# SomUSB2.net
KiCad netlist of a schematic drawn in EAGLE
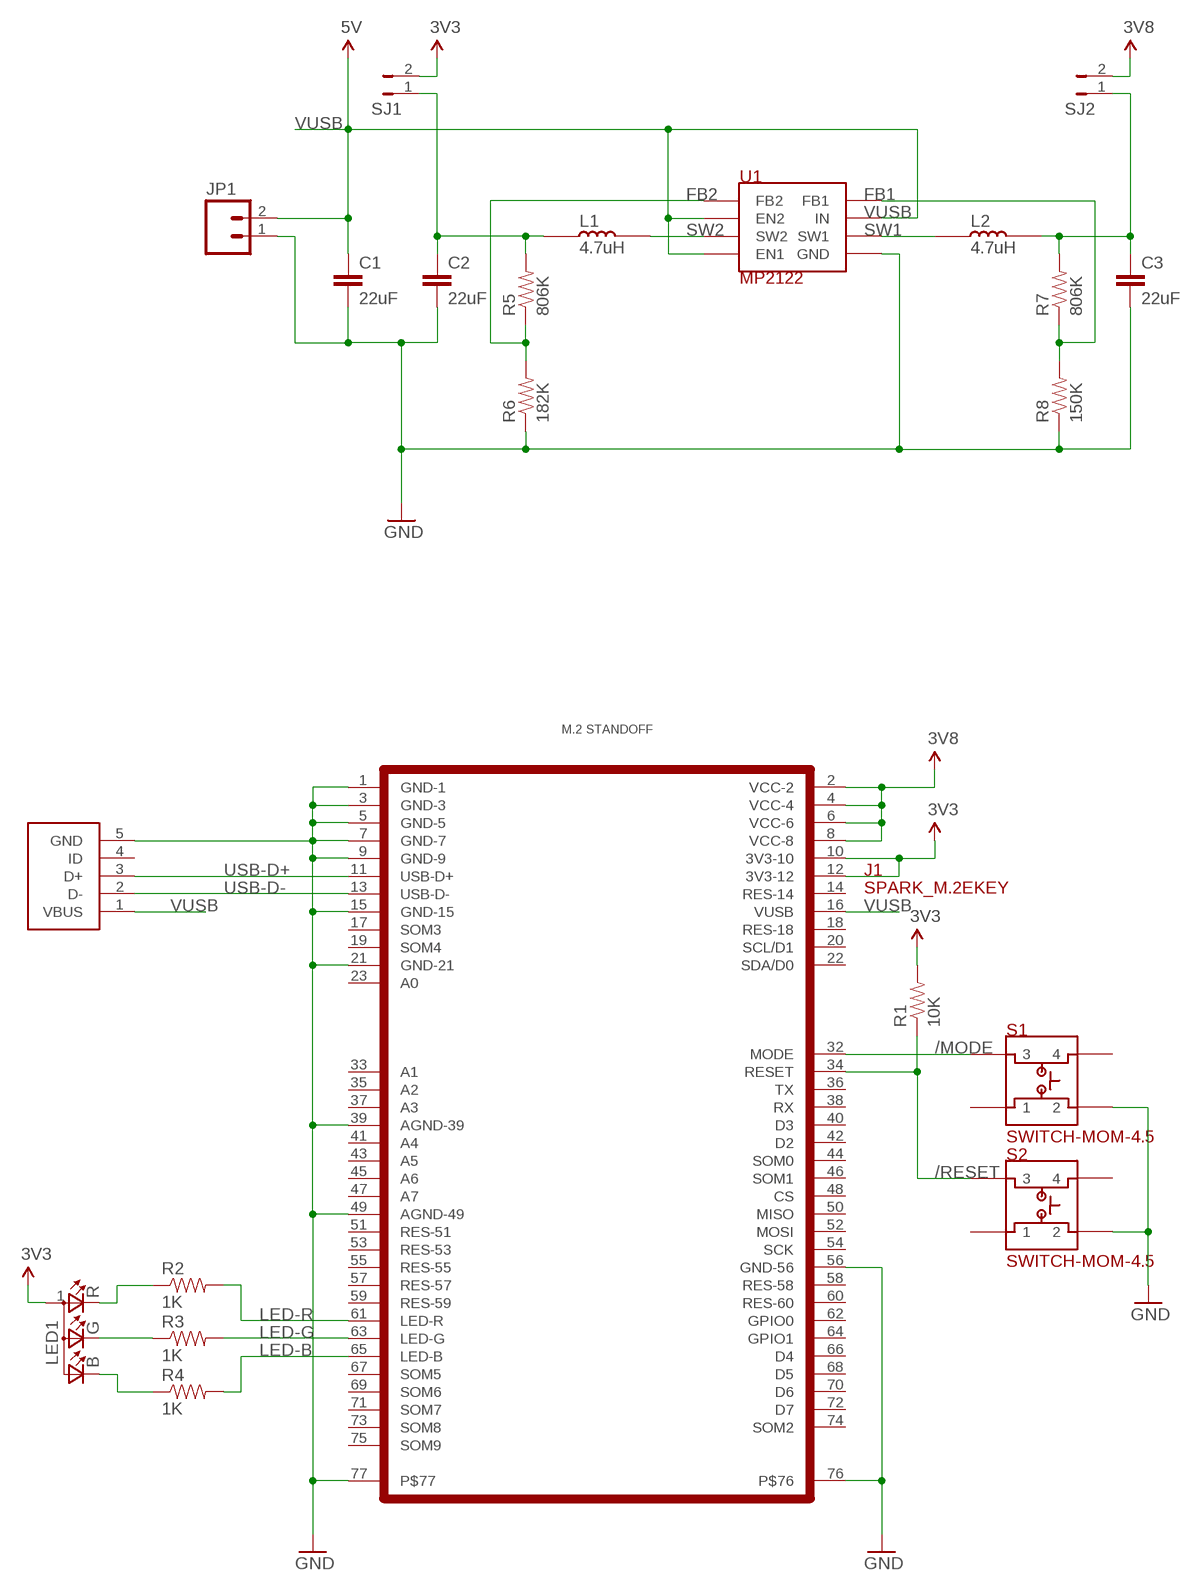
[diagram p0: schematic, sheet 1]

(export (version "E")
  (design (tool "Eeschema 10.0.6"))
  (components
    (comp (ref "C1")
      (value "22uF")
      (footprint "eagle-import:0805")
      (libsource (lib "eagle-import") (part "CAP-22UF-0805"))
    )
    (comp (ref "C2")
      (value "22uF")
      (footprint "eagle-import:0805")
      (libsource (lib "eagle-import") (part "CAP-22UF-0805"))
    )
    (comp (ref "C3")
      (value "22uF")
      (footprint "eagle-import:0805")
      (libsource (lib "eagle-import") (part "CAP-22UF-0805"))
    )
    (comp (ref "J1")
      (value "SPARK_M.2EKEY")
      (footprint "eagle-import:SPARK_M.2EKEY-LESS-CREAM")
      (libsource (lib "eagle-import") (part "SPARK_M.2EKEY"))
    )
    (comp (ref "JP1")
      (value "M02PTH")
      (footprint "eagle-import:1X02")
      (libsource (lib "eagle-import") (part "M02PTH"))
    )
    (comp (ref "L1")
      (value "4.7uH")
      (footprint "eagle-import:1008-BOURNS")
      (libsource (lib "eagle-import") (part "INDUCTOR-4.7UH"))
    )
    (comp (ref "L2")
      (value "4.7uH")
      (footprint "eagle-import:1008-BOURNS")
      (libsource (lib "eagle-import") (part "INDUCTOR-4.7UH"))
    )
    (comp (ref "LED1")
      (value "LED-RGB-CREE-SMD")
      (footprint "eagle-import:LED-RGB-CREE-SMD")
      (libsource (lib "eagle-import") (part "LED-RGB-CREE-SMD"))
    )
    (comp (ref "R1")
      (value "10K")
      (footprint "eagle-import:0603-RES")
      (libsource (lib "eagle-import") (part "RES-10K-06030603"))
    )
    (comp (ref "R2")
      (value "1K")
      (footprint "eagle-import:0603-RES")
      (libsource (lib "eagle-import") (part "RES-1K-0603"))
    )
    (comp (ref "R3")
      (value "1K")
      (footprint "eagle-import:0603-RES")
      (libsource (lib "eagle-import") (part "RES-1K-0603"))
    )
    (comp (ref "R4")
      (value "1K")
      (footprint "eagle-import:0603-RES")
      (libsource (lib "eagle-import") (part "RES-1K-0603"))
    )
    (comp (ref "R5")
      (value "806K")
      (footprint "eagle-import:0603-RES")
      (libsource (lib "eagle-import") (part "RES-806K-0603"))
    )
    (comp (ref "R6")
      (value "182K")
      (footprint "eagle-import:0603-RES")
      (libsource (lib "eagle-import") (part "RES-182K-0603"))
    )
    (comp (ref "R7")
      (value "806K")
      (footprint "eagle-import:0603-RES")
      (libsource (lib "eagle-import") (part "RES-806K-0603"))
    )
    (comp (ref "R8")
      (value "150K")
      (footprint "eagle-import:0603-RES")
      (libsource (lib "eagle-import") (part "RES-150K-0603"))
    )
    (comp (ref "S1")
      (value "SWITCH-MOM-4.5")
      (footprint "eagle-import:SWITCH-MOM-4.5")
      (libsource (lib "eagle-import") (part "SWITCH-MOM-4.5"))
    )
    (comp (ref "S2")
      (value "SWITCH-MOM-4.5")
      (footprint "eagle-import:SWITCH-MOM-4.5")
      (libsource (lib "eagle-import") (part "SWITCH-MOM-4.5"))
    )
    (comp (ref "SJ1")
      (value "JUMPER-PTH-2-NO")
      (footprint "eagle-import:PTH-JUMPER-2-NO_NO_SILK")
      (libsource (lib "eagle-import") (part "JUMPER-PTH-2-NO"))
    )
    (comp (ref "SJ2")
      (value "JUMPER-PTH-2-NO")
      (footprint "eagle-import:PTH-JUMPER-2-NO_NO_SILK")
      (libsource (lib "eagle-import") (part "JUMPER-PTH-2-NO"))
    )
    (comp (ref "U$1")
      (value "M2-STANDOFF")
      (footprint "eagle-import:M2-STANDOFF")
      (libsource (lib "eagle-import") (part "M2-STANDOFF"))
    )
    (comp (ref "U$3")
      (value "USB-MICRO-B-SOCKET-AMPHENOL")
      (footprint "eagle-import:USB-B-SMT-AMPHENOL")
      (libsource (lib "eagle-import") (part "USB-MICRO-B-SOCKET-AMPHENOL"))
    )
    (comp (ref "U1")
      (value "MP2122")
      (footprint "eagle-import:TSOT23-8-MPS")
      (libsource (lib "eagle-import") (part "MPS2112"))
    )
  )
  (nets
    (net (code "1") (name "/FB1") (class "Default")
      (node (ref "R7") (pin "1") (pinfunction "1_1") (pintype "passive"))
      (node (ref "R8") (pin "2") (pinfunction "2_2") (pintype "passive"))
      (node (ref "U1") (pin "8") (pinfunction "FB1_8") (pintype "input"))
    )
    (net (code "2") (name "/FB2") (class "Default")
      (node (ref "R5") (pin "1") (pinfunction "1_1") (pintype "passive"))
      (node (ref "R6") (pin "2") (pinfunction "2_2") (pintype "passive"))
      (node (ref "U1") (pin "1") (pinfunction "FB2_1") (pintype "input"))
    )
    (net (code "3") (name "/LED-B") (class "Default")
      (node (ref "J1") (pin "65") (pinfunction "LED-B_65") (pintype "bidirectional"))
      (node (ref "R4") (pin "2") (pinfunction "2_2") (pintype "passive"))
    )
    (net (code "4") (name "/LED-G") (class "Default")
      (node (ref "J1") (pin "63") (pinfunction "LED-G_63") (pintype "bidirectional"))
      (node (ref "R3") (pin "2") (pinfunction "2_2") (pintype "passive"))
    )
    (net (code "5") (name "/LED-R") (class "Default")
      (node (ref "J1") (pin "61") (pinfunction "LED-R_61") (pintype "bidirectional"))
      (node (ref "R2") (pin "2") (pinfunction "2_2") (pintype "passive"))
    )
    (net (code "6") (name "/SW1") (class "Default")
      (node (ref "L2") (pin "1") (pinfunction "P$1_1") (pintype "passive"))
      (node (ref "U1") (pin "6") (pinfunction "SW1_6") (pintype "output"))
    )
    (net (code "7") (name "/SW2") (class "Default")
      (node (ref "L1") (pin "2") (pinfunction "P$2_2") (pintype "passive"))
      (node (ref "U1") (pin "3") (pinfunction "SW2_3") (pintype "output"))
    )
    (net (code "8") (name "/USB-D+") (class "Default")
      (node (ref "J1") (pin "11") (pinfunction "USB-D+_11") (pintype "bidirectional"))
      (node (ref "U$3") (pin "3") (pinfunction "D+_3") (pintype "passive"))
    )
    (net (code "9") (name "/USB-D-") (class "Default")
      (node (ref "J1") (pin "13") (pinfunction "USB-D-_13") (pintype "bidirectional"))
      (node (ref "U$3") (pin "2") (pinfunction "D-_2") (pintype "passive"))
    )
    (net (code "10") (name "/{slash}MODE") (class "Default")
      (node (ref "J1") (pin "32") (pinfunction "MODE_32") (pintype "bidirectional"))
      (node (ref "S1") (pin "3") (pinfunction "3_3") (pintype "passive"))
    )
    (net (code "11") (name "/{slash}RESET") (class "Default")
      (node (ref "J1") (pin "34") (pinfunction "RESET_34") (pintype "bidirectional"))
      (node (ref "R1") (pin "1") (pinfunction "1_1") (pintype "passive"))
      (node (ref "S2") (pin "3") (pinfunction "3_3") (pintype "passive"))
    )
    (net (code "12") (name "3V3") (class "Default")
      (node (ref "J1") (pin "10") (pinfunction "3V3-10_10") (pintype "bidirectional"))
      (node (ref "J1") (pin "12") (pinfunction "3V3-12_12") (pintype "bidirectional"))
      (node (ref "LED1") (pin "1") (pinfunction "A_1") (pintype "passive"))
      (node (ref "R1") (pin "2") (pinfunction "2_2") (pintype "passive"))
      (node (ref "SJ1") (pin "2") (pinfunction "2_2") (pintype "passive"))
    )
    (net (code "13") (name "3V8") (class "Default")
      (node (ref "J1") (pin "2") (pinfunction "VCC-2_2") (pintype "bidirectional"))
      (node (ref "J1") (pin "4") (pinfunction "VCC-4_4") (pintype "bidirectional"))
      (node (ref "J1") (pin "6") (pinfunction "VCC-6_6") (pintype "bidirectional"))
      (node (ref "J1") (pin "8") (pinfunction "VCC-8_8") (pintype "bidirectional"))
      (node (ref "SJ2") (pin "2") (pinfunction "2_2") (pintype "passive"))
    )
    (net (code "14") (name "5V") (class "Default")
      (node (ref "C1") (pin "1") (pinfunction "1_1") (pintype "passive"))
      (node (ref "J1") (pin "16") (pinfunction "VUSB_16") (pintype "bidirectional"))
      (node (ref "JP1") (pin "2") (pinfunction "2_2") (pintype "passive"))
      (node (ref "U$3") (pin "1") (pinfunction "VBUS_1") (pintype "passive"))
      (node (ref "U1") (pin "2") (pinfunction "EN2_2") (pintype "input"))
      (node (ref "U1") (pin "4") (pinfunction "EN1_4") (pintype "input"))
      (node (ref "U1") (pin "7") (pinfunction "IN_7") (pintype "input"))
    )
    (net (code "15") (name "GND") (class "Default")
      (node (ref "C1") (pin "2") (pinfunction "2_2") (pintype "passive"))
      (node (ref "C2") (pin "2") (pinfunction "2_2") (pintype "passive"))
      (node (ref "C3") (pin "2") (pinfunction "2_2") (pintype "passive"))
      (node (ref "J1") (pin "1") (pinfunction "GND-1_1") (pintype "bidirectional"))
      (node (ref "J1") (pin "15") (pinfunction "GND-15_15") (pintype "bidirectional"))
      (node (ref "J1") (pin "21") (pinfunction "GND-21_21") (pintype "bidirectional"))
      (node (ref "J1") (pin "3") (pinfunction "GND-3_3") (pintype "bidirectional"))
      (node (ref "J1") (pin "39") (pinfunction "AGND-39_39") (pintype "bidirectional"))
      (node (ref "J1") (pin "49") (pinfunction "AGND-49_49") (pintype "bidirectional"))
      (node (ref "J1") (pin "5") (pinfunction "GND-5_5") (pintype "bidirectional"))
      (node (ref "J1") (pin "56") (pinfunction "GND-56_56") (pintype "bidirectional"))
      (node (ref "J1") (pin "7") (pinfunction "GND-7_7") (pintype "bidirectional"))
      (node (ref "J1") (pin "76") (pinfunction "P$76_76") (pintype "power_in"))
      (node (ref "J1") (pin "77") (pinfunction "P$77_77") (pintype "power_in"))
      (node (ref "J1") (pin "9") (pinfunction "GND-9_9") (pintype "bidirectional"))
      (node (ref "JP1") (pin "1") (pinfunction "1_1") (pintype "passive"))
      (node (ref "R6") (pin "1") (pinfunction "1_1") (pintype "passive"))
      (node (ref "R8") (pin "1") (pinfunction "1_1") (pintype "passive"))
      (node (ref "S1") (pin "2") (pinfunction "2_2") (pintype "passive"))
      (node (ref "S2") (pin "2") (pinfunction "2_2") (pintype "passive"))
      (node (ref "U$3") (pin "5") (pinfunction "GND_5") (pintype "passive"))
      (node (ref "U1") (pin "5") (pinfunction "GND_5") (pintype "passive"))
    )
    (net (code "16") (name "Net-(L1-P$1)") (class "Default")
      (node (ref "C2") (pin "1") (pinfunction "1_1") (pintype "passive"))
      (node (ref "L1") (pin "1") (pinfunction "P$1_1") (pintype "passive"))
      (node (ref "R5") (pin "2") (pinfunction "2_2") (pintype "passive"))
      (node (ref "SJ1") (pin "1") (pinfunction "1_1") (pintype "passive"))
    )
    (net (code "17") (name "Net-(L2-P$2)") (class "Default")
      (node (ref "C3") (pin "1") (pinfunction "1_1") (pintype "passive"))
      (node (ref "L2") (pin "2") (pinfunction "P$2_2") (pintype "passive"))
      (node (ref "R7") (pin "2") (pinfunction "2_2") (pintype "passive"))
      (node (ref "SJ2") (pin "1") (pinfunction "1_1") (pintype "passive"))
    )
    (net (code "18") (name "Net-(LED1-B)") (class "Default")
      (node (ref "LED1") (pin "2") (pinfunction "B_2") (pintype "passive"))
      (node (ref "R4") (pin "1") (pinfunction "1_1") (pintype "passive"))
    )
    (net (code "19") (name "Net-(LED1-G)") (class "Default")
      (node (ref "LED1") (pin "3") (pinfunction "G_3") (pintype "passive"))
      (node (ref "R3") (pin "1") (pinfunction "1_1") (pintype "passive"))
    )
    (net (code "20") (name "Net-(LED1-R)") (class "Default")
      (node (ref "LED1") (pin "4") (pinfunction "R_4") (pintype "passive"))
      (node (ref "R2") (pin "1") (pinfunction "1_1") (pintype "passive"))
    )
    (net (code "21") (name "unconnected-(J1-A0-Pad23)") (class "Default")
      (node (ref "J1") (pin "23") (pinfunction "A0_23") (pintype "bidirectional"))
    )
    (net (code "22") (name "unconnected-(J1-A1-Pad33)") (class "Default")
      (node (ref "J1") (pin "33") (pinfunction "A1_33") (pintype "bidirectional"))
    )
    (net (code "23") (name "unconnected-(J1-A2-Pad35)") (class "Default")
      (node (ref "J1") (pin "35") (pinfunction "A2_35") (pintype "bidirectional"))
    )
    (net (code "24") (name "unconnected-(J1-A3-Pad37)") (class "Default")
      (node (ref "J1") (pin "37") (pinfunction "A3_37") (pintype "bidirectional"))
    )
    (net (code "25") (name "unconnected-(J1-A4-Pad41)") (class "Default")
      (node (ref "J1") (pin "41") (pinfunction "A4_41") (pintype "bidirectional"))
    )
    (net (code "26") (name "unconnected-(J1-A5-Pad43)") (class "Default")
      (node (ref "J1") (pin "43") (pinfunction "A5_43") (pintype "bidirectional"))
    )
    (net (code "27") (name "unconnected-(J1-A6-Pad45)") (class "Default")
      (node (ref "J1") (pin "45") (pinfunction "A6_45") (pintype "bidirectional"))
    )
    (net (code "28") (name "unconnected-(J1-A7-Pad47)") (class "Default")
      (node (ref "J1") (pin "47") (pinfunction "A7_47") (pintype "bidirectional"))
    )
    (net (code "29") (name "unconnected-(J1-CS-Pad48)") (class "Default")
      (node (ref "J1") (pin "48") (pinfunction "CS_48") (pintype "bidirectional"))
    )
    (net (code "30") (name "unconnected-(J1-D2-Pad42)") (class "Default")
      (node (ref "J1") (pin "42") (pinfunction "D2_42") (pintype "bidirectional"))
    )
    (net (code "31") (name "unconnected-(J1-D3-Pad40)") (class "Default")
      (node (ref "J1") (pin "40") (pinfunction "D3_40") (pintype "bidirectional"))
    )
    (net (code "32") (name "unconnected-(J1-D4-Pad66)") (class "Default")
      (node (ref "J1") (pin "66") (pinfunction "D4_66") (pintype "bidirectional"))
    )
    (net (code "33") (name "unconnected-(J1-D5-Pad68)") (class "Default")
      (node (ref "J1") (pin "68") (pinfunction "D5_68") (pintype "bidirectional"))
    )
    (net (code "34") (name "unconnected-(J1-D6-Pad70)") (class "Default")
      (node (ref "J1") (pin "70") (pinfunction "D6_70") (pintype "bidirectional"))
    )
    (net (code "35") (name "unconnected-(J1-D7-Pad72)") (class "Default")
      (node (ref "J1") (pin "72") (pinfunction "D7_72") (pintype "bidirectional"))
    )
    (net (code "36") (name "unconnected-(J1-GPIO0-Pad62)") (class "Default")
      (node (ref "J1") (pin "62") (pinfunction "GPIO0_62") (pintype "bidirectional"))
    )
    (net (code "37") (name "unconnected-(J1-GPIO1-Pad64)") (class "Default")
      (node (ref "J1") (pin "64") (pinfunction "GPIO1_64") (pintype "bidirectional"))
    )
    (net (code "38") (name "unconnected-(J1-MISO-Pad50)") (class "Default")
      (node (ref "J1") (pin "50") (pinfunction "MISO_50") (pintype "bidirectional"))
    )
    (net (code "39") (name "unconnected-(J1-MOSI-Pad52)") (class "Default")
      (node (ref "J1") (pin "52") (pinfunction "MOSI_52") (pintype "bidirectional"))
    )
    (net (code "40") (name "unconnected-(J1-RES-14-Pad14)") (class "Default")
      (node (ref "J1") (pin "14") (pinfunction "RES-14_14") (pintype "bidirectional"))
    )
    (net (code "41") (name "unconnected-(J1-RES-18-Pad18)") (class "Default")
      (node (ref "J1") (pin "18") (pinfunction "RES-18_18") (pintype "bidirectional"))
    )
    (net (code "42") (name "unconnected-(J1-RES-51-Pad51)") (class "Default")
      (node (ref "J1") (pin "51") (pinfunction "RES-51_51") (pintype "bidirectional"))
    )
    (net (code "43") (name "unconnected-(J1-RES-53-Pad53)") (class "Default")
      (node (ref "J1") (pin "53") (pinfunction "RES-53_53") (pintype "bidirectional"))
    )
    (net (code "44") (name "unconnected-(J1-RES-55-Pad55)") (class "Default")
      (node (ref "J1") (pin "55") (pinfunction "RES-55_55") (pintype "bidirectional"))
    )
    (net (code "45") (name "unconnected-(J1-RES-57-Pad57)") (class "Default")
      (node (ref "J1") (pin "57") (pinfunction "RES-57_57") (pintype "bidirectional"))
    )
    (net (code "46") (name "unconnected-(J1-RES-58-Pad58)") (class "Default")
      (node (ref "J1") (pin "58") (pinfunction "RES-58_58") (pintype "bidirectional"))
    )
    (net (code "47") (name "unconnected-(J1-RES-59-Pad59)") (class "Default")
      (node (ref "J1") (pin "59") (pinfunction "RES-59_59") (pintype "bidirectional"))
    )
    (net (code "48") (name "unconnected-(J1-RES-60-Pad60)") (class "Default")
      (node (ref "J1") (pin "60") (pinfunction "RES-60_60") (pintype "bidirectional"))
    )
    (net (code "49") (name "unconnected-(J1-RX-Pad38)") (class "Default")
      (node (ref "J1") (pin "38") (pinfunction "RX_38") (pintype "bidirectional"))
    )
    (net (code "50") (name "unconnected-(J1-SCK-Pad54)") (class "Default")
      (node (ref "J1") (pin "54") (pinfunction "SCK_54") (pintype "bidirectional"))
    )
    (net (code "51") (name "unconnected-(J1-SCL{slash}D1-Pad20)") (class "Default")
      (node (ref "J1") (pin "20") (pinfunction "SCL/D1_20") (pintype "bidirectional"))
    )
    (net (code "52") (name "unconnected-(J1-SDA{slash}D0-Pad22)") (class "Default")
      (node (ref "J1") (pin "22") (pinfunction "SDA/D0_22") (pintype "bidirectional"))
    )
    (net (code "53") (name "unconnected-(J1-SOM0-Pad44)") (class "Default")
      (node (ref "J1") (pin "44") (pinfunction "SOM0_44") (pintype "bidirectional"))
    )
    (net (code "54") (name "unconnected-(J1-SOM1-Pad46)") (class "Default")
      (node (ref "J1") (pin "46") (pinfunction "SOM1_46") (pintype "bidirectional"))
    )
    (net (code "55") (name "unconnected-(J1-SOM2-Pad74)") (class "Default")
      (node (ref "J1") (pin "74") (pinfunction "SOM2_74") (pintype "bidirectional"))
    )
    (net (code "56") (name "unconnected-(J1-SOM3-Pad17)") (class "Default")
      (node (ref "J1") (pin "17") (pinfunction "SOM3_17") (pintype "bidirectional"))
    )
    (net (code "57") (name "unconnected-(J1-SOM4-Pad19)") (class "Default")
      (node (ref "J1") (pin "19") (pinfunction "SOM4_19") (pintype "bidirectional"))
    )
    (net (code "58") (name "unconnected-(J1-SOM5-Pad67)") (class "Default")
      (node (ref "J1") (pin "67") (pinfunction "SOM5_67") (pintype "bidirectional"))
    )
    (net (code "59") (name "unconnected-(J1-SOM6-Pad69)") (class "Default")
      (node (ref "J1") (pin "69") (pinfunction "SOM6_69") (pintype "bidirectional"))
    )
    (net (code "60") (name "unconnected-(J1-SOM7-Pad71)") (class "Default")
      (node (ref "J1") (pin "71") (pinfunction "SOM7_71") (pintype "bidirectional"))
    )
    (net (code "61") (name "unconnected-(J1-SOM8-Pad73)") (class "Default")
      (node (ref "J1") (pin "73") (pinfunction "SOM8_73") (pintype "bidirectional"))
    )
    (net (code "62") (name "unconnected-(J1-SOM9-Pad75)") (class "Default")
      (node (ref "J1") (pin "75") (pinfunction "SOM9_75") (pintype "bidirectional"))
    )
    (net (code "63") (name "unconnected-(J1-TX-Pad36)") (class "Default")
      (node (ref "J1") (pin "36") (pinfunction "TX_36") (pintype "bidirectional"))
    )
    (net (code "64") (name "unconnected-(S1-Pad1)") (class "Default")
      (node (ref "S1") (pin "1") (pinfunction "1_1") (pintype "passive"))
    )
    (net (code "65") (name "unconnected-(S1-Pad4)") (class "Default")
      (node (ref "S1") (pin "4") (pinfunction "4_4") (pintype "passive"))
    )
    (net (code "66") (name "unconnected-(S2-Pad1)") (class "Default")
      (node (ref "S2") (pin "1") (pinfunction "1_1") (pintype "passive"))
    )
    (net (code "67") (name "unconnected-(S2-Pad4)") (class "Default")
      (node (ref "S2") (pin "4") (pinfunction "4_4") (pintype "passive"))
    )
    (net (code "68") (name "unconnected-(U$3-ID-Pad4)") (class "Default")
      (node (ref "U$3") (pin "4") (pinfunction "ID_4") (pintype "passive"))
    )
  )
)
